# arduino.net
KiCad netlist of a schematic drawn in EAGLE
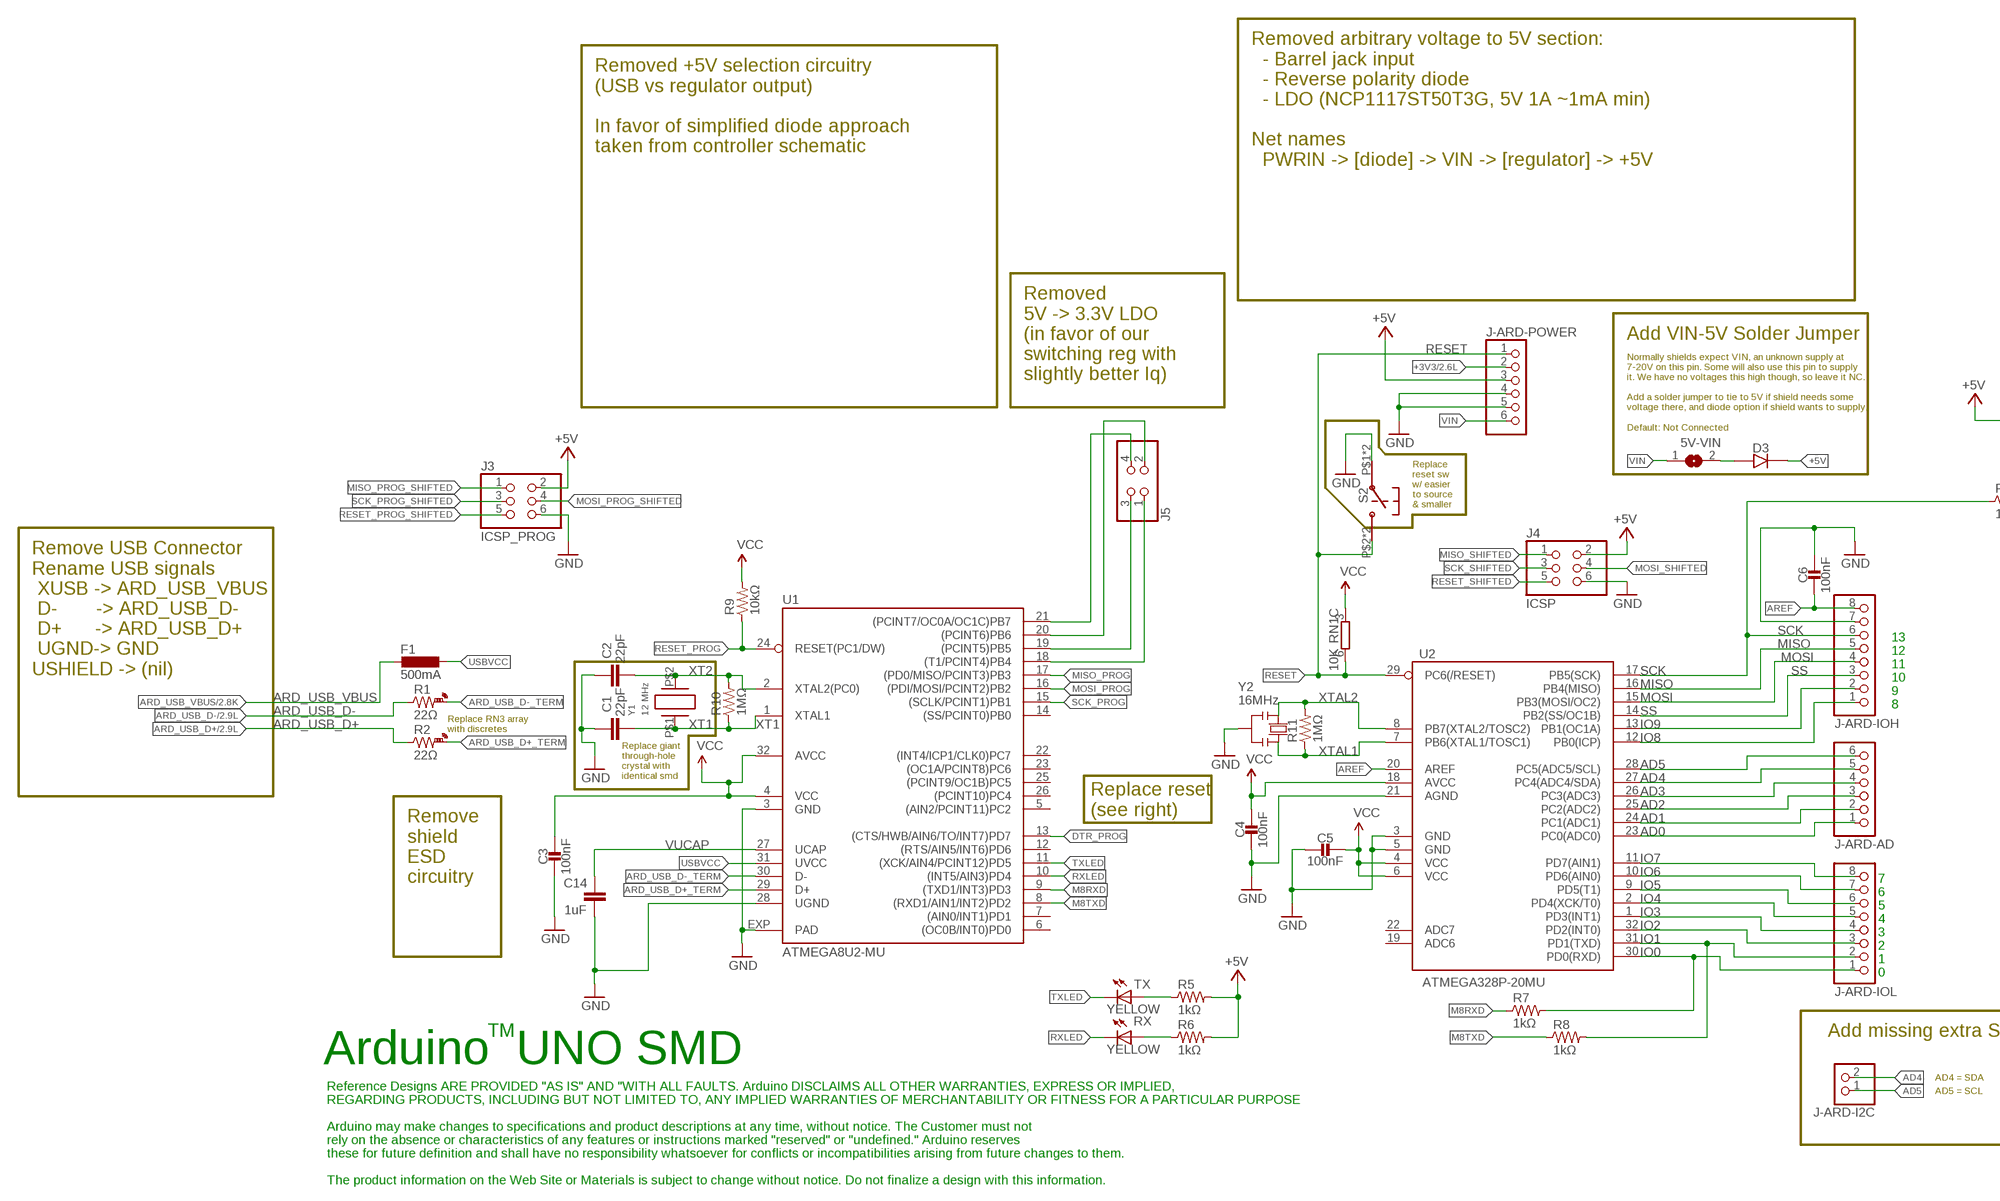
[diagram p0: schematic, sheet 1, part 1 of 2]
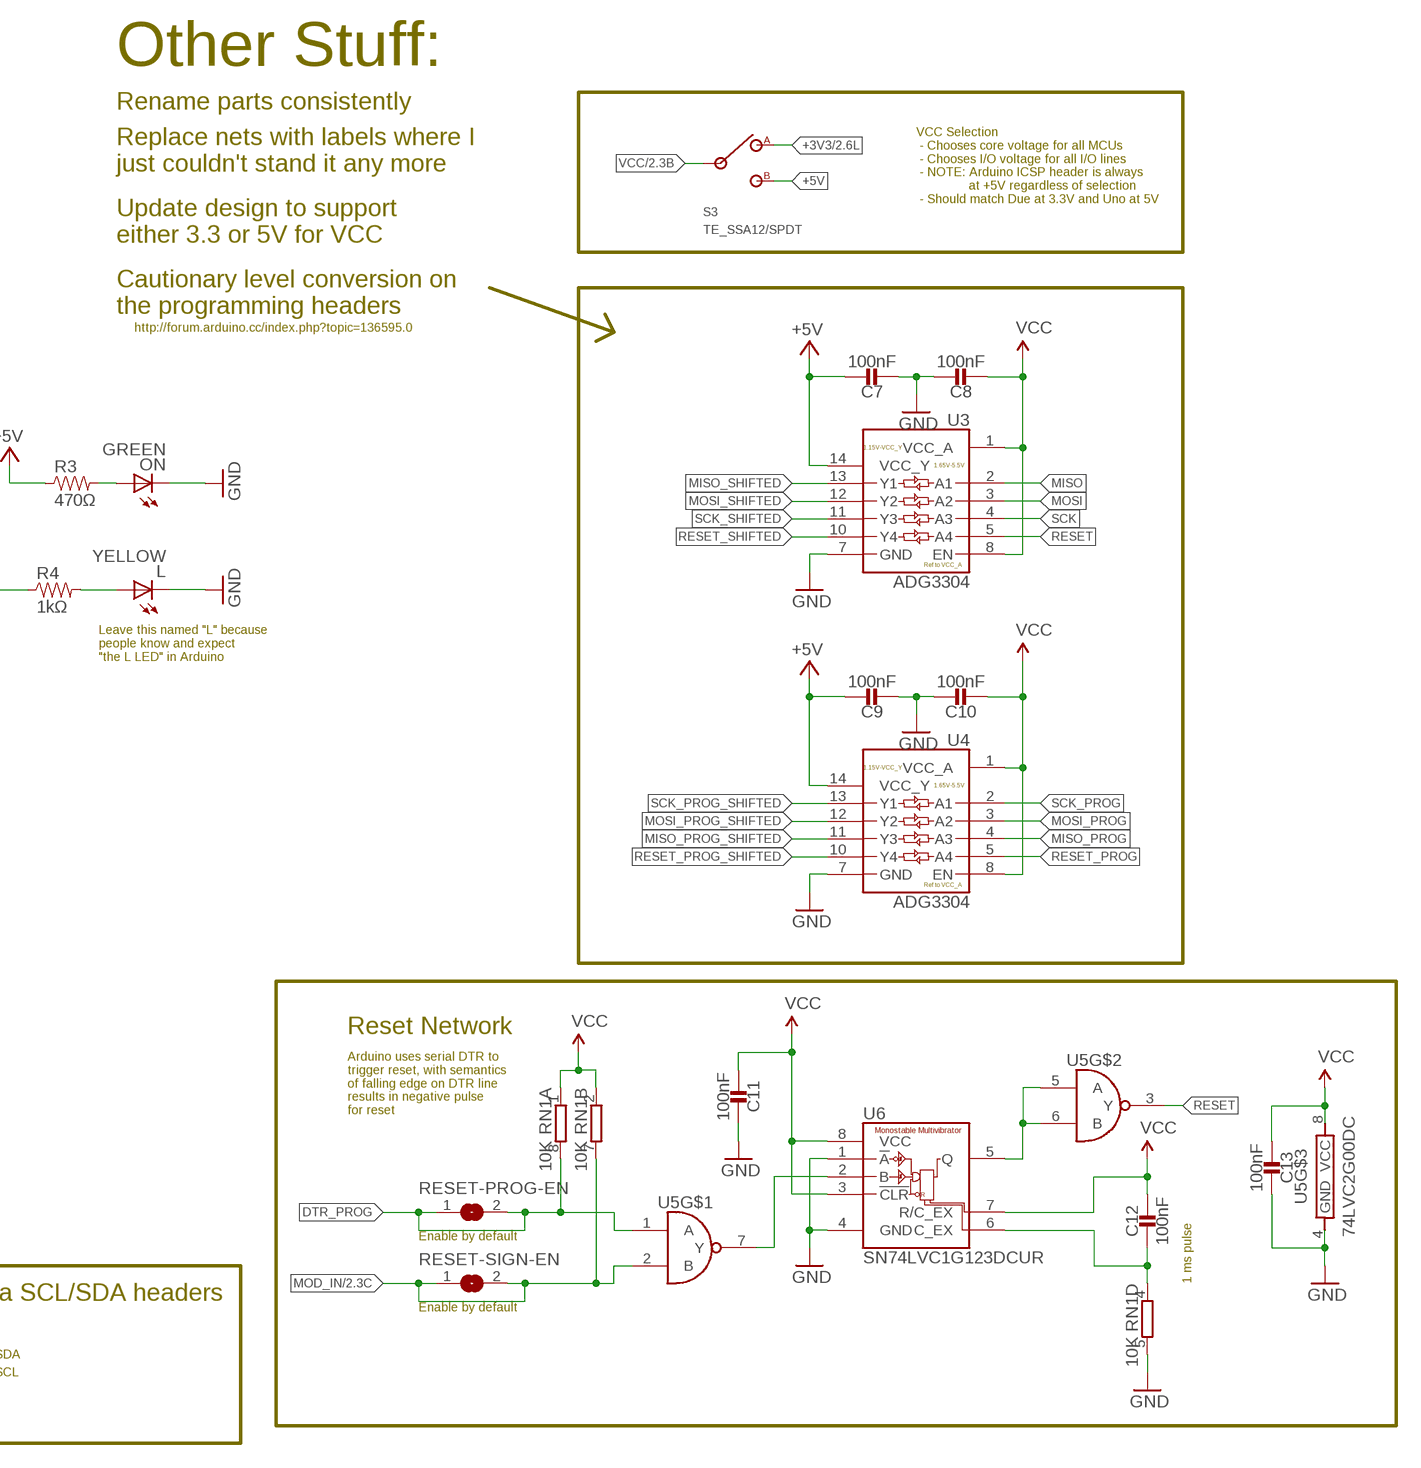
[diagram p1: schematic, sheet 1, part 2 of 2]
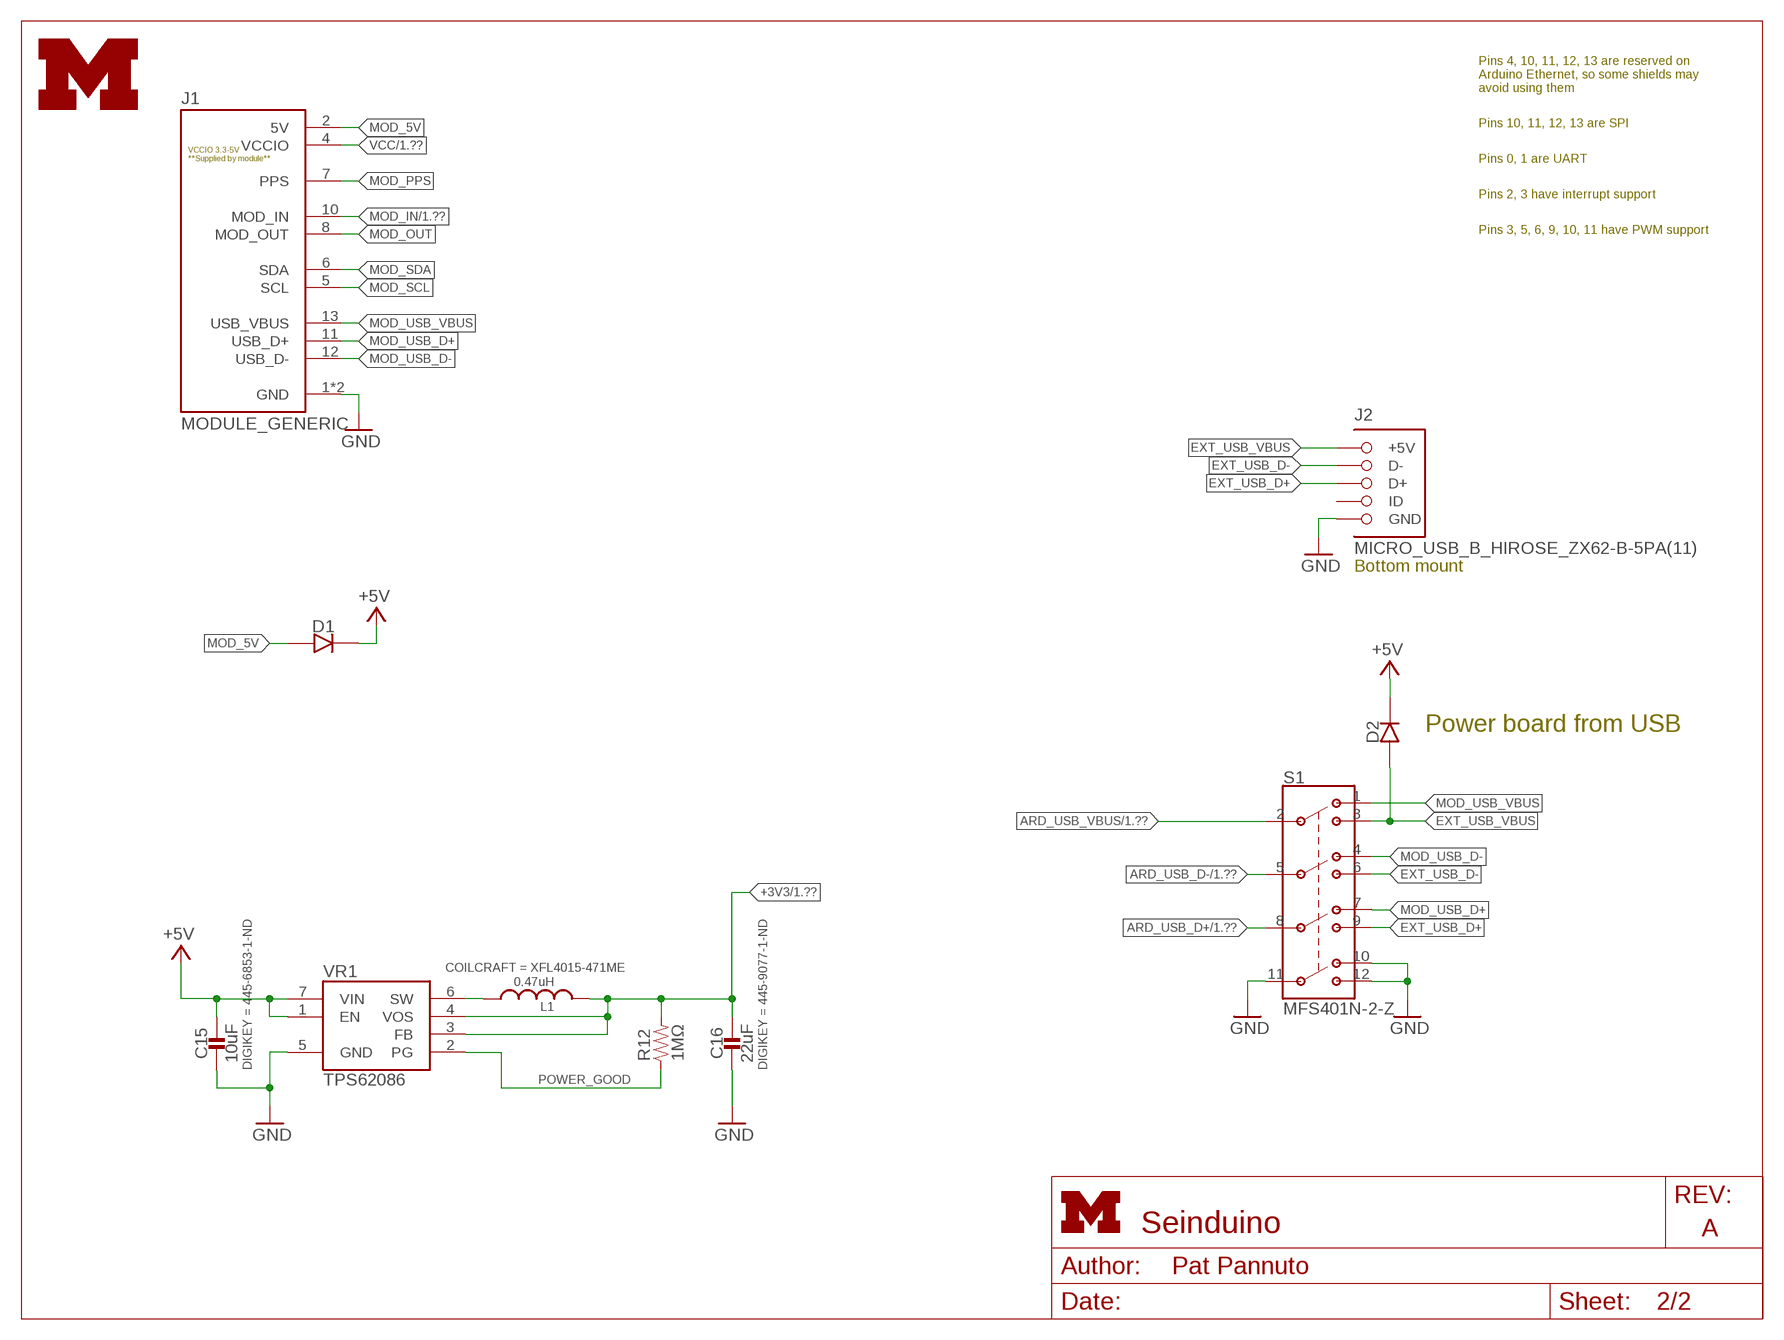
[diagram p2: schematic, sheet 2]

(export (version "E")
  (design (tool "Eeschema 10.0.6"))
  (components
    (comp (ref "5V-VIN")
      (value "SJ")
      (footprint "eagle-import:SJ")
      (libsource (lib "eagle-import") (part "SJ"))
    )
    (comp (ref "C1")
      (value "22pF")
      (footprint "eagle-import:C0603-ROUND")
      (libsource (lib "eagle-import") (part "C-EU0603-RND"))
    )
    (comp (ref "C2")
      (value "22pF")
      (footprint "eagle-import:C0603-ROUND")
      (libsource (lib "eagle-import") (part "C-EU0603-RND"))
    )
    (comp (ref "C3")
      (value "100nF")
      (footprint "eagle-import:0603_CAP")
      (libsource (lib "eagle-import") (part "CAPACITOR0603_CAP"))
    )
    (comp (ref "C4")
      (value "100nF")
      (footprint "eagle-import:0603_CAP")
      (libsource (lib "eagle-import") (part "CAPACITOR0603_CAP"))
    )
    (comp (ref "C5")
      (value "100nF")
      (footprint "eagle-import:0603_CAP")
      (libsource (lib "eagle-import") (part "CAPACITOR0603_CAP"))
    )
    (comp (ref "C6")
      (value "100nF")
      (footprint "eagle-import:0603_CAP")
      (libsource (lib "eagle-import") (part "CAPACITOR0603_CAP"))
    )
    (comp (ref "C7")
      (value "100nF")
      (footprint "eagle-import:0603_CAP")
      (libsource (lib "eagle-import") (part "CAPACITOR0603_CAP"))
    )
    (comp (ref "C8")
      (value "100nF")
      (footprint "eagle-import:0603_CAP")
      (libsource (lib "eagle-import") (part "CAPACITOR0603_CAP"))
    )
    (comp (ref "C9")
      (value "100nF")
      (footprint "eagle-import:0603_CAP")
      (libsource (lib "eagle-import") (part "CAPACITOR0603_CAP"))
    )
    (comp (ref "C10")
      (value "100nF")
      (footprint "eagle-import:0603_CAP")
      (libsource (lib "eagle-import") (part "CAPACITOR0603_CAP"))
    )
    (comp (ref "C11")
      (value "100nF")
      (footprint "eagle-import:0603_CAP")
      (libsource (lib "eagle-import") (part "CAPACITOR0603_CAP"))
    )
    (comp (ref "C12")
      (value "100nF")
      (footprint "eagle-import:0603_CAP")
      (libsource (lib "eagle-import") (part "CAPACITOR0603_CAP"))
    )
    (comp (ref "C13")
      (value "100nF")
      (footprint "eagle-import:0603_CAP")
      (libsource (lib "eagle-import") (part "CAPACITOR0603_CAP"))
    )
    (comp (ref "C14")
      (value "1uF")
      (footprint "eagle-import:C0603-ROUND")
      (libsource (lib "eagle-import") (part "C-EU0603-RND"))
    )
    (comp (ref "D3")
      (value "DIODE")
      (footprint "eagle-import:0402_DIODE")
      (libsource (lib "eagle-import") (part "DIODE"))
    )
    (comp (ref "F1")
      (value "500mA")
      (footprint "eagle-import:L1812")
      (libsource (lib "eagle-import") (part "L-EUL1812"))
    )
    (comp (ref "J-ARD-AD")
      (value "PINHD-1X6")
      (footprint "eagle-import:1X06")
      (libsource (lib "eagle-import") (part "PINHD-1X6"))
    )
    (comp (ref "J-ARD-I2C")
      (value "PINHD-1X2")
      (footprint "eagle-import:1X02")
      (libsource (lib "eagle-import") (part "PINHD-1X2"))
    )
    (comp (ref "J-ARD-IOH")
      (value "PINHD-1X8")
      (footprint "eagle-import:1X08")
      (libsource (lib "eagle-import") (part "PINHD-1X8"))
    )
    (comp (ref "J-ARD-IOL")
      (value "PINHD-1X8")
      (footprint "eagle-import:1X08")
      (libsource (lib "eagle-import") (part "PINHD-1X8"))
    )
    (comp (ref "J-ARD-POWER")
      (value "PINHD-1X6")
      (footprint "eagle-import:1X06")
      (libsource (lib "eagle-import") (part "PINHD-1X6"))
    )
    (comp (ref "J3")
      (value "ICSP_PROG")
      (footprint "eagle-import:2X03")
      (libsource (lib "eagle-import") (part "PINHD-2X3"))
    )
    (comp (ref "J4")
      (value "ICSP")
      (footprint "eagle-import:2X03")
      (libsource (lib "eagle-import") (part "PINHD-2X3"))
    )
    (comp (ref "J5")
      (value "PINHD-2X2")
      (footprint "eagle-import:2X02")
      (libsource (lib "eagle-import") (part "PINHD-2X2"))
    )
    (comp (ref "L")
      (value "YELLOW")
      (footprint "eagle-import:CHIP-LED0805")
      (libsource (lib "eagle-import") (part "LEDCHIP-LED0805"))
    )
    (comp (ref "ON")
      (value "GREEN")
      (footprint "eagle-import:CHIP-LED0805")
      (libsource (lib "eagle-import") (part "LEDCHIP-LED0805"))
    )
    (comp (ref "R1")
      (value "22Ω")
      (footprint "eagle-import:0402_RES-HIGH_SPEED")
      (libsource (lib "eagle-import") (part "RESISTOR-HIGH_SPEED0402"))
    )
    (comp (ref "R2")
      (value "22Ω")
      (footprint "eagle-import:0402_RES-HIGH_SPEED")
      (libsource (lib "eagle-import") (part "RESISTOR-HIGH_SPEED0402"))
    )
    (comp (ref "R3")
      (value "470Ω")
      (footprint "eagle-import:0603-RES")
      (libsource (lib "eagle-import") (part "RESISTOR0603_RES"))
    )
    (comp (ref "R4")
      (value "1kΩ")
      (footprint "eagle-import:0603-RES")
      (libsource (lib "eagle-import") (part "RESISTOR0603_RES"))
    )
    (comp (ref "R5")
      (value "1kΩ")
      (footprint "eagle-import:0603-RES")
      (libsource (lib "eagle-import") (part "RESISTOR0603_RES"))
    )
    (comp (ref "R6")
      (value "1kΩ")
      (footprint "eagle-import:0603-RES")
      (libsource (lib "eagle-import") (part "RESISTOR0603_RES"))
    )
    (comp (ref "R7")
      (value "1kΩ")
      (footprint "eagle-import:0603-RES")
      (libsource (lib "eagle-import") (part "RESISTOR0603_RES"))
    )
    (comp (ref "R8")
      (value "1kΩ")
      (footprint "eagle-import:0603-RES")
      (libsource (lib "eagle-import") (part "RESISTOR0603_RES"))
    )
    (comp (ref "R9")
      (value "10kΩ")
      (footprint "eagle-import:0603-RES")
      (libsource (lib "eagle-import") (part "RESISTOR0603_RES"))
    )
    (comp (ref "R10")
      (value "1MΩ")
      (footprint "eagle-import:0603-RES")
      (libsource (lib "eagle-import") (part "RESISTOR0603_RES"))
    )
    (comp (ref "R11")
      (value "1MΩ")
      (footprint "eagle-import:0603-RES")
      (libsource (lib "eagle-import") (part "RESISTOR0603_RES"))
    )
    (comp (ref "RESET-PROG-EN")
      (value "SJ")
      (footprint "eagle-import:SJ")
      (libsource (lib "eagle-import") (part "SJ"))
    )
    (comp (ref "RESET-SIGN-EN")
      (value "SJ")
      (footprint "eagle-import:SJ")
      (libsource (lib "eagle-import") (part "SJ"))
    )
    (comp (ref "RN1")
      (value "10K")
      (footprint "eagle-import:CAY16")
      (fields (field (name "DIGIKEY") "CAY16-103J4GLFCT-ND"))
      (libsource (lib "eagle-import") (part "4R-NCAY16"))
    )
    (comp (ref "RX")
      (value "YELLOW")
      (footprint "eagle-import:CHIP-LED0805")
      (libsource (lib "eagle-import") (part "LEDCHIP-LED0805"))
    )
    (comp (ref "S2")
      (value "EVQP2")
      (footprint "eagle-import:EVQP2")
      (libsource (lib "eagle-import") (part "EVQP2"))
    )
    (comp (ref "S3")
      (value "TE_SSA12/SPDT")
      (footprint "eagle-import:TE_SSA12_SPDT")
      (libsource (lib "eagle-import") (part "TE_SSA12/SPDT"))
    )
    (comp (ref "TX")
      (value "YELLOW")
      (footprint "eagle-import:CHIP-LED0805")
      (libsource (lib "eagle-import") (part "LEDCHIP-LED0805"))
    )
    (comp (ref "U1")
      (value "ATMEGA8U2-MU")
      (footprint "eagle-import:QFN32")
      (libsource (lib "eagle-import") (part "ATMEGA8U2-MU"))
    )
    (comp (ref "U2")
      (value "ATMEGA328P-20MU")
      (footprint "eagle-import:MLF32")
      (libsource (lib "eagle-import") (part "MEGA8-MI"))
    )
    (comp (ref "U3")
      (value "ADG3304")
      (footprint "eagle-import:TSSOP-14_5MM")
      (libsource (lib "eagle-import") (part "ADG3304"))
    )
    (comp (ref "U4")
      (value "ADG3304")
      (footprint "eagle-import:TSSOP-14_5MM")
      (libsource (lib "eagle-import") (part "ADG3304"))
    )
    (comp (ref "U5")
      (value "74LVC2G00DC")
      (footprint "eagle-import:VSSOP-8")
      (libsource (lib "eagle-import") (part "74LVC2G00DC"))
    )
    (comp (ref "U6")
      (value "SN74LVC1G123DCUR")
      (footprint "eagle-import:VFSOP-8")
      (libsource (lib "eagle-import") (part "SN74LVC1G123DCUR"))
    )
    (comp (ref "Y1")
      (value "12 MHz")
      (footprint "eagle-import:ABM3")
      (libsource (lib "eagle-import") (part "ABM3"))
    )
    (comp (ref "Y2")
      (value "16MHz")
      (footprint "eagle-import:RESONATOR")
      (libsource (lib "eagle-import") (part "RESONATORMU"))
    )
    (comp (ref "C15")
      (value "10uF")
      (footprint "eagle-import:0603_CAP")
      (fields (field (name "DIGIKEY") "445-6853-1-ND"))
      (libsource (lib "eagle-import") (part "CAPACITOR0603_CAP"))
    )
    (comp (ref "C16")
      (value "22uF")
      (footprint "eagle-import:0603_CAP")
      (fields (field (name "DIGIKEY") "445-9077-1-ND"))
      (libsource (lib "eagle-import") (part "CAPACITOR0603_CAP"))
    )
    (comp (ref "D1")
      (value "DIODE")
      (footprint "eagle-import:0402_DIODE")
      (libsource (lib "eagle-import") (part "DIODE"))
    )
    (comp (ref "D2")
      (value "DIODE")
      (footprint "eagle-import:0402_DIODE")
      (libsource (lib "eagle-import") (part "DIODE"))
    )
    (comp (ref "J1")
      (value "MODULE_GENERIC")
      (footprint "eagle-import:MODULE_GENERIC")
      (libsource (lib "eagle-import") (part "MODULE_GENERIC"))
    )
    (comp (ref "J2")
      (value "MICRO_USB_B_HIROSE_ZX62-B-5PA(11)")
      (footprint "eagle-import:USB_MICRO_B-HIROSE-ZX62-B-5PA(11)")
      (libsource (lib "eagle-import") (part "MICRO_USB_B_HIROSE_ZX62-B-5PA(11)"))
    )
    (comp (ref "L1")
      (value "0.47uH")
      (footprint "eagle-import:XFL4015")
      (fields (field (name "COILCRAFT") "XFL4015-471ME"))
      (libsource (lib "eagle-import") (part "INDUCTORXFL4015"))
    )
    (comp (ref "LOGO1")
      (value "UMICH_SOLID_MEDIUM")
      (footprint "eagle-import:UMICH_SOLID_200MIL")
      (libsource (lib "eagle-import") (part "UMICH_SOLID_MEDIUM"))
    )
    (comp (ref "R12")
      (value "1MΩ")
      (footprint "eagle-import:0603-RES")
      (libsource (lib "eagle-import") (part "RESISTOR0603_RES"))
    )
    (comp (ref "S1")
      (value "MFS401N-2-Z")
      (footprint "eagle-import:MFS401N-2-Z")
      (libsource (lib "eagle-import") (part "MFS401N-2-Z"))
    )
    (comp (ref "VR1")
      (value "TPS62086")
      (footprint "eagle-import:RLT0007A")
      (libsource (lib "eagle-import") (part "TPS62086"))
    )
  )
  (nets
    (net (code "1") (name "+3V3") (class "Default")
      (node (ref "C16") (pin "1") (pinfunction "1_1") (pintype "bidirectional"))
      (node (ref "J-ARD-POWER") (pin "2") (pinfunction "2_2") (pintype "passive"))
      (node (ref "L1") (pin "2") (pinfunction "2_2") (pintype "bidirectional"))
      (node (ref "R12") (pin "2") (pinfunction "2_2") (pintype "passive"))
      (node (ref "S3") (pin "1") (pinfunction "A_1") (pintype "bidirectional"))
      (node (ref "VR1") (pin "3") (pinfunction "FB_3") (pintype "bidirectional"))
      (node (ref "VR1") (pin "4") (pinfunction "VOS_4") (pintype "bidirectional"))
    )
    (net (code "2") (name "+5V") (class "Default")
      (node (ref "C15") (pin "1") (pinfunction "1_1") (pintype "bidirectional"))
      (node (ref "C7") (pin "1") (pinfunction "1_1") (pintype "bidirectional"))
      (node (ref "C9") (pin "1") (pinfunction "1_1") (pintype "bidirectional"))
      (node (ref "D1") (pin "CATHODE") (pinfunction "CATHODE_CATHODE") (pintype "bidirectional"))
      (node (ref "D2") (pin "CATHODE") (pinfunction "CATHODE_CATHODE") (pintype "bidirectional"))
      (node (ref "D3") (pin "CATHODE") (pinfunction "CATHODE_CATHODE") (pintype "bidirectional"))
      (node (ref "J-ARD-POWER") (pin "3") (pinfunction "3_3") (pintype "passive"))
      (node (ref "J3") (pin "2") (pinfunction "2_2") (pintype "passive"))
      (node (ref "J4") (pin "2") (pinfunction "2_2") (pintype "passive"))
      (node (ref "R3") (pin "1") (pinfunction "1_1") (pintype "passive"))
      (node (ref "R5") (pin "2") (pinfunction "2_2") (pintype "passive"))
      (node (ref "R6") (pin "2") (pinfunction "2_2") (pintype "passive"))
      (node (ref "S3") (pin "2") (pinfunction "B_2") (pintype "bidirectional"))
      (node (ref "U3") (pin "14") (pinfunction "VCC_Y_14") (pintype "bidirectional"))
      (node (ref "U4") (pin "14") (pinfunction "VCC_Y_14") (pintype "bidirectional"))
      (node (ref "VR1") (pin "1") (pinfunction "EN_1") (pintype "bidirectional"))
      (node (ref "VR1") (pin "7") (pinfunction "VIN_7") (pintype "bidirectional"))
    )
    (net (code "3") (name "AD0") (class "Default")
      (node (ref "J-ARD-AD") (pin "1") (pinfunction "1_1") (pintype "passive"))
      (node (ref "U2") (pin "23") (pinfunction "PC0(ADC0)_23") (pintype "bidirectional"))
    )
    (net (code "4") (name "AD1") (class "Default")
      (node (ref "J-ARD-AD") (pin "2") (pinfunction "2_2") (pintype "passive"))
      (node (ref "U2") (pin "24") (pinfunction "PC1(ADC1)_24") (pintype "bidirectional"))
    )
    (net (code "5") (name "AD2") (class "Default")
      (node (ref "J-ARD-AD") (pin "3") (pinfunction "3_3") (pintype "passive"))
      (node (ref "U2") (pin "25") (pinfunction "PC2(ADC2)_25") (pintype "bidirectional"))
    )
    (net (code "6") (name "AD3") (class "Default")
      (node (ref "J-ARD-AD") (pin "4") (pinfunction "4_4") (pintype "passive"))
      (node (ref "U2") (pin "26") (pinfunction "PC3(ADC3)_26") (pintype "bidirectional"))
    )
    (net (code "7") (name "AD4") (class "Default")
      (node (ref "J-ARD-AD") (pin "5") (pinfunction "5_5") (pintype "passive"))
      (node (ref "J-ARD-I2C") (pin "2") (pinfunction "2_2") (pintype "passive"))
      (node (ref "U2") (pin "27") (pinfunction "PC4(ADC4/SDA)_27") (pintype "bidirectional"))
    )
    (net (code "8") (name "AD5") (class "Default")
      (node (ref "J-ARD-AD") (pin "6") (pinfunction "6_6") (pintype "passive"))
      (node (ref "J-ARD-I2C") (pin "1") (pinfunction "1_1") (pintype "passive"))
      (node (ref "U2") (pin "28") (pinfunction "PC5(ADC5/SCL)_28") (pintype "bidirectional"))
    )
    (net (code "9") (name "ARD_USB_D+") (class "Default")
      (node (ref "R2") (pin "2") (pinfunction "P$2_2") (pintype "passive"))
      (node (ref "S1") (pin "8") (pinfunction "3P_8") (pintype "bidirectional"))
    )
    (net (code "10") (name "ARD_USB_D+_TERM") (class "Default")
      (node (ref "R2") (pin "1") (pinfunction "P$1_1") (pintype "passive"))
      (node (ref "U1") (pin "29") (pinfunction "D+_29") (pintype "bidirectional"))
    )
    (net (code "11") (name "ARD_USB_D-") (class "Default")
      (node (ref "R1") (pin "2") (pinfunction "P$2_2") (pintype "passive"))
      (node (ref "S1") (pin "5") (pinfunction "2P_5") (pintype "bidirectional"))
    )
    (net (code "12") (name "ARD_USB_D-_TERM") (class "Default")
      (node (ref "R1") (pin "1") (pinfunction "P$1_1") (pintype "passive"))
      (node (ref "U1") (pin "30") (pinfunction "D-_30") (pintype "bidirectional"))
    )
    (net (code "13") (name "ARD_USB_VBUS") (class "Default")
      (node (ref "F1") (pin "2") (pinfunction "2_2") (pintype "passive"))
      (node (ref "S1") (pin "2") (pinfunction "1P_2") (pintype "bidirectional"))
    )
    (net (code "14") (name "AREF") (class "Default")
      (node (ref "C6") (pin "2") (pinfunction "2_2") (pintype "bidirectional"))
      (node (ref "J-ARD-IOH") (pin "8") (pinfunction "8_8") (pintype "passive"))
      (node (ref "U2") (pin "20") (pinfunction "AREF_20") (pintype "bidirectional"))
    )
    (net (code "15") (name "DTR_PROG") (class "Default")
      (node (ref "RESET-PROG-EN") (pin "1") (pinfunction "1_1") (pintype "passive"))
      (node (ref "RESET-PROG-EN") (pin "2") (pinfunction "2_2") (pintype "passive"))
      (node (ref "RN1") (pin "8") (pinfunction "2_8") (pintype "passive"))
      (node (ref "U1") (pin "13") (pinfunction "(CTS/HWB/AIN6/TO/INT7)PD7_13") (pintype "bidirectional"))
      (node (ref "U5") (pin "1") (pinfunction "A_1") (pintype "bidirectional"))
    )
    (net (code "16") (name "EXT_USB_D+") (class "Default")
      (node (ref "J2") (pin "3") (pinfunction "D+_3") (pintype "bidirectional"))
      (node (ref "S1") (pin "9") (pinfunction "3TB_9") (pintype "bidirectional"))
    )
    (net (code "17") (name "EXT_USB_D-") (class "Default")
      (node (ref "J2") (pin "2") (pinfunction "D-_2") (pintype "bidirectional"))
      (node (ref "S1") (pin "6") (pinfunction "2TB_6") (pintype "bidirectional"))
    )
    (net (code "18") (name "EXT_USB_VBUS") (class "Default")
      (node (ref "D2") (pin "ANODE") (pinfunction "ANODE_ANODE") (pintype "bidirectional"))
      (node (ref "J2") (pin "1") (pinfunction "+5V_1") (pintype "bidirectional"))
      (node (ref "S1") (pin "3") (pinfunction "1TB_3") (pintype "bidirectional"))
    )
    (net (code "19") (name "GND") (class "Default")
      (node (ref "C1") (pin "2") (pinfunction "2_2") (pintype "passive"))
      (node (ref "C10") (pin "1") (pinfunction "1_1") (pintype "bidirectional"))
      (node (ref "C11") (pin "1") (pinfunction "1_1") (pintype "bidirectional"))
      (node (ref "C13") (pin "1") (pinfunction "1_1") (pintype "bidirectional"))
      (node (ref "C14") (pin "2") (pinfunction "2_2") (pintype "passive"))
      (node (ref "C15") (pin "2") (pinfunction "2_2") (pintype "bidirectional"))
      (node (ref "C16") (pin "2") (pinfunction "2_2") (pintype "bidirectional"))
      (node (ref "C2") (pin "2") (pinfunction "2_2") (pintype "passive"))
      (node (ref "C3") (pin "2") (pinfunction "2_2") (pintype "bidirectional"))
      (node (ref "C4") (pin "2") (pinfunction "2_2") (pintype "bidirectional"))
      (node (ref "C5") (pin "2") (pinfunction "2_2") (pintype "bidirectional"))
      (node (ref "C6") (pin "1") (pinfunction "1_1") (pintype "bidirectional"))
      (node (ref "C7") (pin "2") (pinfunction "2_2") (pintype "bidirectional"))
      (node (ref "C8") (pin "1") (pinfunction "1_1") (pintype "bidirectional"))
      (node (ref "C9") (pin "2") (pinfunction "2_2") (pintype "bidirectional"))
      (node (ref "J-ARD-IOH") (pin "7") (pinfunction "7_7") (pintype "passive"))
      (node (ref "J-ARD-POWER") (pin "4") (pinfunction "4_4") (pintype "passive"))
      (node (ref "J-ARD-POWER") (pin "5") (pinfunction "5_5") (pintype "passive"))
      (node (ref "J1") (pin "1") (pinfunction "GND_1") (pintype "bidirectional"))
      (node (ref "J1") (pin "14") (pinfunction "GND_14") (pintype "bidirectional"))
      (node (ref "J2") (pin "5") (pinfunction "GND_5") (pintype "bidirectional"))
      (node (ref "J3") (pin "6") (pinfunction "6_6") (pintype "passive"))
      (node (ref "J4") (pin "6") (pinfunction "6_6") (pintype "passive"))
      (node (ref "L") (pin "C") (pinfunction "C_C") (pintype "passive"))
      (node (ref "ON") (pin "C") (pinfunction "C_C") (pintype "passive"))
      (node (ref "RN1") (pin "5") (pinfunction "2_5") (pintype "passive"))
      (node (ref "S1") (pin "10") (pinfunction "4TA_10") (pintype "bidirectional"))
      (node (ref "S1") (pin "11") (pinfunction "4P_11") (pintype "bidirectional"))
      (node (ref "S1") (pin "12") (pinfunction "4TB_12") (pintype "bidirectional"))
      (node (ref "S2") (pin "P$1") (pinfunction "P$1_P$1") (pintype "passive"))
      (node (ref "S2") (pin "P$3") (pinfunction "P$1_P$3") (pintype "passive"))
      (node (ref "U1") (pin "28") (pinfunction "UGND_28") (pintype "power_in"))
      (node (ref "U1") (pin "3") (pinfunction "GND_3") (pintype "power_in"))
      (node (ref "U1") (pin "EXP") (pinfunction "PAD_EXP") (pintype "power_in"))
      (node (ref "U2") (pin "21") (pinfunction "AGND_21") (pintype "bidirectional"))
      (node (ref "U2") (pin "3") (pinfunction "GND_3") (pintype "bidirectional"))
      (node (ref "U2") (pin "5") (pinfunction "GND_5") (pintype "bidirectional"))
      (node (ref "U3") (pin "7") (pinfunction "GND_7") (pintype "bidirectional"))
      (node (ref "U4") (pin "7") (pinfunction "GND_7") (pintype "bidirectional"))
      (node (ref "U5") (pin "4") (pinfunction "GND_4") (pintype "bidirectional"))
      (node (ref "U6") (pin "1") (pinfunction "~{A}_1") (pintype "bidirectional"))
      (node (ref "U6") (pin "4") (pinfunction "GND_4") (pintype "bidirectional"))
      (node (ref "VR1") (pin "5") (pinfunction "GND_5") (pintype "bidirectional"))
      (node (ref "Y2") (pin "2") (pinfunction "2_2") (pintype "passive"))
    )
    (net (code "20") (name "IO0") (class "Default")
      (node (ref "J-ARD-IOL") (pin "1") (pinfunction "1_1") (pintype "passive"))
      (node (ref "R7") (pin "2") (pinfunction "2_2") (pintype "passive"))
      (node (ref "U2") (pin "30") (pinfunction "PD0(RXD)_30") (pintype "bidirectional"))
    )
    (net (code "21") (name "IO1") (class "Default")
      (node (ref "J-ARD-IOL") (pin "2") (pinfunction "2_2") (pintype "passive"))
      (node (ref "R8") (pin "2") (pinfunction "2_2") (pintype "passive"))
      (node (ref "U2") (pin "31") (pinfunction "PD1(TXD)_31") (pintype "bidirectional"))
    )
    (net (code "22") (name "IO2") (class "Default")
      (node (ref "J-ARD-IOL") (pin "3") (pinfunction "3_3") (pintype "passive"))
      (node (ref "U2") (pin "32") (pinfunction "PD2(INT0)_32") (pintype "bidirectional"))
    )
    (net (code "23") (name "IO3") (class "Default")
      (node (ref "J-ARD-IOL") (pin "4") (pinfunction "4_4") (pintype "passive"))
      (node (ref "U2") (pin "1") (pinfunction "PD3(INT1)_1") (pintype "bidirectional"))
    )
    (net (code "24") (name "IO4") (class "Default")
      (node (ref "J-ARD-IOL") (pin "5") (pinfunction "5_5") (pintype "passive"))
      (node (ref "U2") (pin "2") (pinfunction "PD4(XCK/T0)_2") (pintype "bidirectional"))
    )
    (net (code "25") (name "IO5") (class "Default")
      (node (ref "J-ARD-IOL") (pin "6") (pinfunction "6_6") (pintype "passive"))
      (node (ref "U2") (pin "9") (pinfunction "PD5(T1)_9") (pintype "bidirectional"))
    )
    (net (code "26") (name "IO6") (class "Default")
      (node (ref "J-ARD-IOL") (pin "7") (pinfunction "7_7") (pintype "passive"))
      (node (ref "U2") (pin "10") (pinfunction "PD6(AIN0)_10") (pintype "bidirectional"))
    )
    (net (code "27") (name "IO7") (class "Default")
      (node (ref "J-ARD-IOL") (pin "8") (pinfunction "8_8") (pintype "passive"))
      (node (ref "U2") (pin "11") (pinfunction "PD7(AIN1)_11") (pintype "bidirectional"))
    )
    (net (code "28") (name "IO8") (class "Default")
      (node (ref "J-ARD-IOH") (pin "1") (pinfunction "1_1") (pintype "passive"))
      (node (ref "U2") (pin "12") (pinfunction "PB0(ICP)_12") (pintype "bidirectional"))
    )
    (net (code "29") (name "IO9") (class "Default")
      (node (ref "J-ARD-IOH") (pin "2") (pinfunction "2_2") (pintype "passive"))
      (node (ref "U2") (pin "13") (pinfunction "PB1(OC1A)_13") (pintype "bidirectional"))
    )
    (net (code "30") (name "M8RXD") (class "Default")
      (node (ref "R7") (pin "1") (pinfunction "1_1") (pintype "passive"))
      (node (ref "U1") (pin "9") (pinfunction "(TXD1/INT3)PD3_9") (pintype "bidirectional"))
    )
    (net (code "31") (name "M8TXD") (class "Default")
      (node (ref "R8") (pin "1") (pinfunction "1_1") (pintype "passive"))
      (node (ref "U1") (pin "8") (pinfunction "(RXD1/AIN1/INT2)PD2_8") (pintype "bidirectional"))
    )
    (net (code "32") (name "MISO") (class "Default")
      (node (ref "J-ARD-IOH") (pin "5") (pinfunction "5_5") (pintype "passive"))
      (node (ref "U2") (pin "16") (pinfunction "PB4(MISO)_16") (pintype "bidirectional"))
      (node (ref "U3") (pin "2") (pinfunction "A1_2") (pintype "bidirectional"))
    )
    (net (code "33") (name "MISO_PROG") (class "Default")
      (node (ref "U1") (pin "17") (pinfunction "(PD0/MISO/PCINT3)PB3_17") (pintype "bidirectional"))
      (node (ref "U4") (pin "4") (pinfunction "A3_4") (pintype "bidirectional"))
    )
    (net (code "34") (name "MISO_PROG_SHIFTED") (class "Default")
      (node (ref "J3") (pin "1") (pinfunction "1_1") (pintype "passive"))
      (node (ref "U4") (pin "11") (pinfunction "Y3_11") (pintype "bidirectional"))
    )
    (net (code "35") (name "MISO_SHIFTED") (class "Default")
      (node (ref "J4") (pin "1") (pinfunction "1_1") (pintype "passive"))
      (node (ref "U3") (pin "13") (pinfunction "Y1_13") (pintype "bidirectional"))
    )
    (net (code "36") (name "MOD_5V") (class "Default")
      (node (ref "D1") (pin "ANODE") (pinfunction "ANODE_ANODE") (pintype "bidirectional"))
      (node (ref "J1") (pin "2") (pinfunction "5V_2") (pintype "bidirectional"))
    )
    (net (code "37") (name "MOD_IN") (class "Default")
      (node (ref "J1") (pin "10") (pinfunction "MOD_IN_10") (pintype "bidirectional"))
      (node (ref "RESET-SIGN-EN") (pin "1") (pinfunction "1_1") (pintype "passive"))
      (node (ref "RESET-SIGN-EN") (pin "2") (pinfunction "2_2") (pintype "passive"))
      (node (ref "RN1") (pin "7") (pinfunction "2_7") (pintype "passive"))
      (node (ref "U5") (pin "2") (pinfunction "B_2") (pintype "bidirectional"))
    )
    (net (code "38") (name "MOD_OUT") (class "Default")
      (node (ref "J1") (pin "8") (pinfunction "MOD_OUT_8") (pintype "bidirectional"))
    )
    (net (code "39") (name "MOD_PPS") (class "Default")
      (node (ref "J1") (pin "7") (pinfunction "PPS_7") (pintype "bidirectional"))
    )
    (net (code "40") (name "MOD_SCL") (class "Default")
      (node (ref "J1") (pin "5") (pinfunction "SCL_5") (pintype "bidirectional"))
    )
    (net (code "41") (name "MOD_SDA") (class "Default")
      (node (ref "J1") (pin "6") (pinfunction "SDA_6") (pintype "bidirectional"))
    )
    (net (code "42") (name "MOD_USB_D+") (class "Default")
      (node (ref "J1") (pin "11") (pinfunction "USB_D+_11") (pintype "bidirectional"))
      (node (ref "S1") (pin "7") (pinfunction "3TA_7") (pintype "bidirectional"))
    )
    (net (code "43") (name "MOD_USB_D-") (class "Default")
      (node (ref "J1") (pin "12") (pinfunction "USB_D-_12") (pintype "bidirectional"))
      (node (ref "S1") (pin "4") (pinfunction "2TA_4") (pintype "bidirectional"))
    )
    (net (code "44") (name "MOD_USB_VBUS") (class "Default")
      (node (ref "J1") (pin "13") (pinfunction "USB_VBUS_13") (pintype "bidirectional"))
      (node (ref "S1") (pin "1") (pinfunction "1TA_1") (pintype "bidirectional"))
    )
    (net (code "45") (name "MOSI") (class "Default")
      (node (ref "J-ARD-IOH") (pin "4") (pinfunction "4_4") (pintype "passive"))
      (node (ref "U2") (pin "15") (pinfunction "PB3(MOSI/OC2)_15") (pintype "bidirectional"))
      (node (ref "U3") (pin "3") (pinfunction "A2_3") (pintype "bidirectional"))
    )
    (net (code "46") (name "MOSI_PROG") (class "Default")
      (node (ref "U1") (pin "16") (pinfunction "(PDI/MOSI/PCINT2)PB2_16") (pintype "bidirectional"))
      (node (ref "U4") (pin "3") (pinfunction "A2_3") (pintype "bidirectional"))
    )
    (net (code "47") (name "MOSI_PROG_SHIFTED") (class "Default")
      (node (ref "J3") (pin "4") (pinfunction "4_4") (pintype "passive"))
      (node (ref "U4") (pin "12") (pinfunction "Y2_12") (pintype "bidirectional"))
    )
    (net (code "48") (name "MOSI_SHIFTED") (class "Default")
      (node (ref "J4") (pin "4") (pinfunction "4_4") (pintype "passive"))
      (node (ref "U3") (pin "12") (pinfunction "Y2_12") (pintype "bidirectional"))
    )
    (net (code "49") (name "Net-(5V-VIN-Pad2)") (class "Default")
      (node (ref "5V-VIN") (pin "2") (pinfunction "2_2") (pintype "passive"))
      (node (ref "D3") (pin "ANODE") (pinfunction "ANODE_ANODE") (pintype "bidirectional"))
    )
    (net (code "50") (name "Net-(L-PadA)") (class "Default")
      (node (ref "L") (pin "A") (pinfunction "A_A") (pintype "passive"))
      (node (ref "R4") (pin "2") (pinfunction "2_2") (pintype "passive"))
    )
    (net (code "51") (name "Net-(ON-PadA)") (class "Default")
      (node (ref "ON") (pin "A") (pinfunction "A_A") (pintype "passive"))
      (node (ref "R3") (pin "2") (pinfunction "2_2") (pintype "passive"))
    )
    (net (code "52") (name "Net-(R5-Pad1)") (class "Default")
      (node (ref "R5") (pin "1") (pinfunction "1_1") (pintype "passive"))
      (node (ref "TX") (pin "A") (pinfunction "A_A") (pintype "passive"))
    )
    (net (code "53") (name "Net-(R6-Pad1)") (class "Default")
      (node (ref "R6") (pin "1") (pinfunction "1_1") (pintype "passive"))
      (node (ref "RX") (pin "A") (pinfunction "A_A") (pintype "passive"))
    )
    (net (code "54") (name "Net-(RN1D-1)") (class "Default")
      (node (ref "C12") (pin "2") (pinfunction "2_2") (pintype "bidirectional"))
      (node (ref "RN1") (pin "4") (pinfunction "1_4") (pintype "passive"))
      (node (ref "U6") (pin "6") (pinfunction "C_EX_6") (pintype "bidirectional"))
    )
    (net (code "55") (name "Net-(U1-(PCINT5)PB5)") (class "Default")
      (node (ref "J5") (pin "3") (pinfunction "3_3") (pintype "passive"))
      (node (ref "U1") (pin "19") (pinfunction "(PCINT5)PB5_19") (pintype "bidirectional"))
    )
    (net (code "56") (name "Net-(U1-(PCINT6)PB6)") (class "Default")
      (node (ref "J5") (pin "2") (pinfunction "2_2") (pintype "passive"))
      (node (ref "U1") (pin "20") (pinfunction "(PCINT6)PB6_20") (pintype "bidirectional"))
    )
    (net (code "57") (name "Net-(U1-(PCINT7{slash}OC0A{slash}OC1C)PB7)") (class "Default")
      (node (ref "J5") (pin "4") (pinfunction "4_4") (pintype "passive"))
      (node (ref "U1") (pin "21") (pinfunction "(PCINT7/OC0A/OC1C)PB7_21") (pintype "bidirectional"))
    )
    (net (code "58") (name "Net-(U1-(T1{slash}PCINT4)PB4)") (class "Default")
      (node (ref "J5") (pin "1") (pinfunction "1_1") (pintype "passive"))
      (node (ref "U1") (pin "18") (pinfunction "(T1/PCINT4)PB4_18") (pintype "bidirectional"))
    )
    (net (code "59") (name "Net-(U5A-Y)") (class "Default")
      (node (ref "U5") (pin "7") (pinfunction "Y_7") (pintype "bidirectional"))
      (node (ref "U6") (pin "2") (pinfunction "B_2") (pintype "bidirectional"))
    )
    (net (code "60") (name "Net-(U5B-A)") (class "Default")
      (node (ref "U5") (pin "5") (pinfunction "A_5") (pintype "bidirectional"))
      (node (ref "U5") (pin "6") (pinfunction "B_6") (pintype "bidirectional"))
      (node (ref "U6") (pin "5") (pinfunction "Q_5") (pintype "bidirectional"))
    )
    (net (code "61") (name "Net-(VR1-SW)") (class "Default")
      (node (ref "L1") (pin "1") (pinfunction "1_1") (pintype "bidirectional"))
      (node (ref "VR1") (pin "6") (pinfunction "SW_6") (pintype "bidirectional"))
    )
    (net (code "62") (name "POWER_GOOD") (class "Default")
      (node (ref "R12") (pin "1") (pinfunction "1_1") (pintype "passive"))
      (node (ref "VR1") (pin "2") (pinfunction "PG_2") (pintype "bidirectional"))
    )
    (net (code "63") (name "RESET") (class "Default")
      (node (ref "J-ARD-POWER") (pin "1") (pinfunction "1_1") (pintype "passive"))
      (node (ref "RN1") (pin "6") (pinfunction "2_6") (pintype "passive"))
      (node (ref "S2") (pin "P$2") (pinfunction "P$2_P$2") (pintype "passive"))
      (node (ref "S2") (pin "P$4") (pinfunction "P$2_P$4") (pintype "passive"))
      (node (ref "U2") (pin "29") (pinfunction "PC6(/RESET)_29") (pintype "bidirectional"))
      (node (ref "U3") (pin "5") (pinfunction "A4_5") (pintype "bidirectional"))
      (node (ref "U5") (pin "3") (pinfunction "Y_3") (pintype "bidirectional"))
    )
    (net (code "64") (name "RESET_PROG") (class "Default")
      (node (ref "R9") (pin "1") (pinfunction "1_1") (pintype "passive"))
      (node (ref "U1") (pin "24") (pinfunction "RESET(PC1/DW)_24") (pintype "input"))
      (node (ref "U4") (pin "5") (pinfunction "A4_5") (pintype "bidirectional"))
    )
    (net (code "65") (name "RESET_PROG_SHIFTED") (class "Default")
      (node (ref "J3") (pin "5") (pinfunction "5_5") (pintype "passive"))
      (node (ref "U4") (pin "10") (pinfunction "Y4_10") (pintype "bidirectional"))
    )
    (net (code "66") (name "RESET_SHIFTED") (class "Default")
      (node (ref "J4") (pin "5") (pinfunction "5_5") (pintype "passive"))
      (node (ref "U3") (pin "10") (pinfunction "Y4_10") (pintype "bidirectional"))
    )
    (net (code "67") (name "RXLED") (class "Default")
      (node (ref "RX") (pin "C") (pinfunction "C_C") (pintype "passive"))
      (node (ref "U1") (pin "10") (pinfunction "(INT5/AIN3)PD4_10") (pintype "bidirectional"))
    )
    (net (code "68") (name "SCK") (class "Default")
      (node (ref "J-ARD-IOH") (pin "6") (pinfunction "6_6") (pintype "passive"))
      (node (ref "R4") (pin "1") (pinfunction "1_1") (pintype "passive"))
      (node (ref "U2") (pin "17") (pinfunction "PB5(SCK)_17") (pintype "bidirectional"))
      (node (ref "U3") (pin "4") (pinfunction "A3_4") (pintype "bidirectional"))
    )
    (net (code "69") (name "SCK_PROG") (class "Default")
      (node (ref "U1") (pin "15") (pinfunction "(SCLK/PCINT1)PB1_15") (pintype "bidirectional"))
      (node (ref "U4") (pin "2") (pinfunction "A1_2") (pintype "bidirectional"))
    )
    (net (code "70") (name "SCK_PROG_SHIFTED") (class "Default")
      (node (ref "J3") (pin "3") (pinfunction "3_3") (pintype "passive"))
      (node (ref "U4") (pin "13") (pinfunction "Y1_13") (pintype "bidirectional"))
    )
    (net (code "71") (name "SCK_SHIFTED") (class "Default")
      (node (ref "J4") (pin "3") (pinfunction "3_3") (pintype "passive"))
      (node (ref "U3") (pin "11") (pinfunction "Y3_11") (pintype "bidirectional"))
    )
    (net (code "72") (name "SS") (class "Default")
      (node (ref "J-ARD-IOH") (pin "3") (pinfunction "3_3") (pintype "passive"))
      (node (ref "U2") (pin "14") (pinfunction "PB2(SS/OC1B)_14") (pintype "bidirectional"))
    )
    (net (code "73") (name "TXLED") (class "Default")
      (node (ref "TX") (pin "C") (pinfunction "C_C") (pintype "passive"))
      (node (ref "U1") (pin "11") (pinfunction "(XCK/AIN4/PCINT12)PD5_11") (pintype "bidirectional"))
    )
    (net (code "74") (name "USBVCC") (class "Default")
      (node (ref "F1") (pin "1") (pinfunction "1_1") (pintype "passive"))
      (node (ref "U1") (pin "31") (pinfunction "UVCC_31") (pintype "power_in"))
    )
    (net (code "75") (name "VCC") (class "Default")
      (node (ref "C10") (pin "2") (pinfunction "2_2") (pintype "bidirectional"))
      (node (ref "C11") (pin "2") (pinfunction "2_2") (pintype "bidirectional"))
      (node (ref "C12") (pin "1") (pinfunction "1_1") (pintype "bidirectional"))
      (node (ref "C13") (pin "2") (pinfunction "2_2") (pintype "bidirectional"))
      (node (ref "C3") (pin "1") (pinfunction "1_1") (pintype "bidirectional"))
      (node (ref "C4") (pin "1") (pinfunction "1_1") (pintype "bidirectional"))
      (node (ref "C5") (pin "1") (pinfunction "1_1") (pintype "bidirectional"))
      (node (ref "C8") (pin "2") (pinfunction "2_2") (pintype "bidirectional"))
      (node (ref "J1") (pin "4") (pinfunction "VCCIO_4") (pintype "bidirectional"))
      (node (ref "R9") (pin "2") (pinfunction "2_2") (pintype "passive"))
      (node (ref "RN1") (pin "1") (pinfunction "1_1") (pintype "passive"))
      (node (ref "RN1") (pin "2") (pinfunction "1_2") (pintype "passive"))
      (node (ref "RN1") (pin "3") (pinfunction "1_3") (pintype "passive"))
      (node (ref "S3") (pin "IN") (pinfunction "IN_IN") (pintype "bidirectional"))
      (node (ref "U1") (pin "32") (pinfunction "AVCC_32") (pintype "power_in"))
      (node (ref "U1") (pin "4") (pinfunction "VCC_4") (pintype "power_in"))
      (node (ref "U2") (pin "18") (pinfunction "AVCC_18") (pintype "bidirectional"))
      (node (ref "U2") (pin "4") (pinfunction "VCC_4") (pintype "bidirectional"))
      (node (ref "U2") (pin "6") (pinfunction "VCC_6") (pintype "bidirectional"))
      (node (ref "U3") (pin "1") (pinfunction "VCC_A_1") (pintype "bidirectional"))
      (node (ref "U3") (pin "8") (pinfunction "EN_8") (pintype "bidirectional"))
      (node (ref "U4") (pin "1") (pinfunction "VCC_A_1") (pintype "bidirectional"))
      (node (ref "U4") (pin "8") (pinfunction "EN_8") (pintype "bidirectional"))
      (node (ref "U5") (pin "8") (pinfunction "VCC_8") (pintype "bidirectional"))
      (node (ref "U6") (pin "3") (pinfunction "~{CLR}_3") (pintype "bidirectional"))
      (node (ref "U6") (pin "7") (pinfunction "R/C_EX_7") (pintype "bidirectional"))
      (node (ref "U6") (pin "8") (pinfunction "VCC_8") (pintype "bidirectional"))
    )
    (net (code "76") (name "VIN") (class "Default")
      (node (ref "5V-VIN") (pin "1") (pinfunction "1_1") (pintype "passive"))
      (node (ref "J-ARD-POWER") (pin "6") (pinfunction "6_6") (pintype "passive"))
    )
    (net (code "77") (name "VUCAP") (class "Default")
      (node (ref "C14") (pin "1") (pinfunction "1_1") (pintype "passive"))
      (node (ref "U1") (pin "27") (pinfunction "UCAP_27") (pintype "passive"))
    )
    (net (code "78") (name "XT1") (class "Default")
      (node (ref "C1") (pin "1") (pinfunction "1_1") (pintype "passive"))
      (node (ref "R10") (pin "1") (pinfunction "1_1") (pintype "passive"))
      (node (ref "U1") (pin "1") (pinfunction "XTAL1_1") (pintype "bidirectional"))
      (node (ref "Y1") (pin "P$1") (pinfunction "1_P$1") (pintype "bidirectional"))
    )
    (net (code "79") (name "XT2") (class "Default")
      (node (ref "C2") (pin "1") (pinfunction "1_1") (pintype "passive"))
      (node (ref "R10") (pin "2") (pinfunction "2_2") (pintype "passive"))
      (node (ref "U1") (pin "2") (pinfunction "XTAL2(PC0)_2") (pintype "bidirectional"))
      (node (ref "Y1") (pin "P$2") (pinfunction "2_P$2") (pintype "bidirectional"))
    )
    (net (code "80") (name "XTAL1") (class "Default")
      (node (ref "R11") (pin "1") (pinfunction "1_1") (pintype "passive"))
      (node (ref "U2") (pin "7") (pinfunction "PB6(XTAL1/TOSC1)_7") (pintype "bidirectional"))
      (node (ref "Y2") (pin "3") (pinfunction "3_3") (pintype "passive"))
    )
    (net (code "81") (name "XTAL2") (class "Default")
      (node (ref "R11") (pin "2") (pinfunction "2_2") (pintype "passive"))
      (node (ref "U2") (pin "8") (pinfunction "PB7(XTAL2/TOSC2)_8") (pintype "bidirectional"))
      (node (ref "Y2") (pin "1") (pinfunction "1_1") (pintype "passive"))
    )
    (net (code "82") (name "unconnected-(J2-ID-Pad4)") (class "Default")
      (node (ref "J2") (pin "4") (pinfunction "ID_4") (pintype "bidirectional"))
    )
    (net (code "83") (name "unconnected-(U1-(AIN0{slash}INT1)PD1-Pad7)") (class "Default")
      (node (ref "U1") (pin "7") (pinfunction "(AIN0/INT1)PD1_7") (pintype "bidirectional"))
    )
    (net (code "84") (name "unconnected-(U1-(AIN2{slash}PCINT11)PC2-Pad5)") (class "Default")
      (node (ref "U1") (pin "5") (pinfunction "(AIN2/PCINT11)PC2_5") (pintype "bidirectional"))
    )
    (net (code "85") (name "unconnected-(U1-(INT4{slash}ICP1{slash}CLK0)PC7-Pad22)") (class "Default")
      (node (ref "U1") (pin "22") (pinfunction "(INT4/ICP1/CLK0)PC7_22") (pintype "bidirectional"))
    )
    (net (code "86") (name "unconnected-(U1-(OC0B{slash}INT0)PD0-Pad6)") (class "Default")
      (node (ref "U1") (pin "6") (pinfunction "(OC0B/INT0)PD0_6") (pintype "bidirectional"))
    )
    (net (code "87") (name "unconnected-(U1-(OC1A{slash}PCINT8)PC6-Pad23)") (class "Default")
      (node (ref "U1") (pin "23") (pinfunction "(OC1A/PCINT8)PC6_23") (pintype "bidirectional"))
    )
    (net (code "88") (name "unconnected-(U1-(PCINT9{slash}OC1B)PC5-Pad25)") (class "Default")
      (node (ref "U1") (pin "25") (pinfunction "(PCINT9/OC1B)PC5_25") (pintype "bidirectional"))
    )
    (net (code "89") (name "unconnected-(U1-(PCINT10)PC4-Pad26)") (class "Default")
      (node (ref "U1") (pin "26") (pinfunction "(PCINT10)PC4_26") (pintype "bidirectional"))
    )
    (net (code "90") (name "unconnected-(U1-(RTS{slash}AIN5{slash}INT6)PD6-Pad12)") (class "Default")
      (node (ref "U1") (pin "12") (pinfunction "(RTS/AIN5/INT6)PD6_12") (pintype "bidirectional"))
    )
    (net (code "91") (name "unconnected-(U1-(SS{slash}PCINT0)PB0-Pad14)") (class "Default")
      (node (ref "U1") (pin "14") (pinfunction "(SS/PCINT0)PB0_14") (pintype "bidirectional"))
    )
    (net (code "92") (name "unconnected-(U2-ADC6-Pad19)") (class "Default")
      (node (ref "U2") (pin "19") (pinfunction "ADC6_19") (pintype "bidirectional"))
    )
    (net (code "93") (name "unconnected-(U2-ADC7-Pad22)") (class "Default")
      (node (ref "U2") (pin "22") (pinfunction "ADC7_22") (pintype "bidirectional"))
    )
  )
)
